# Khoi-nguon.net
KiCad netlist of a schematic drawn in Altium Designer
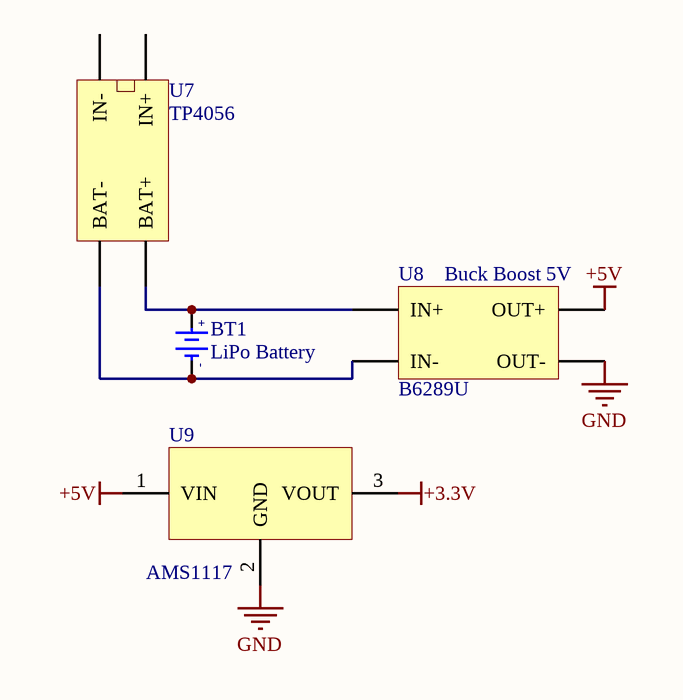
[diagram p0: Khoi-nguon.SchDoc]

(export (version "E")
  (design (tool "Eeschema 10.0.6"))
  (components
    (comp (ref "BT1")
      (value "LiPo Battery")
      (footprint "PIN3V")
      (description "Battery 3VDC")
      (libsource (lib "LIBRARY1") (part "PIN 3V"))
    )
    (comp (ref "U7")
      (value "TP4056")
      (description "Module sac pin")
      (libsource (lib "iuh-thuc-hanh") (part "TP4056"))
    )
    (comp (ref "U8")
      (value "B6289U")
      (description "Module Buck Boost 5V")
      (libsource (lib "iuh-thuc-hanh") (part "B6289U"))
    )
    (comp (ref "U9") (value "AMS1117") (libsource (lib "iuh-thuc-hanh") (part "AMS1117")))
  )
  (nets
    (net (code "1") (name "+3.3V") (class "Default")
      (node (ref "U9") (pin "3") (pinfunction "VOUT_3") (pintype "passive"))
    )
    (net (code "2") (name "+5V") (class "Default")
      (node (ref "U8") (pin "3") (pinfunction "OUT+_3") (pintype "passive"))
      (node (ref "U9") (pin "1") (pinfunction "VIN_1") (pintype "passive"))
    )
    (net (code "3") (name "GND") (class "Default")
      (node (ref "U8") (pin "4") (pinfunction "OUT-_4") (pintype "passive"))
      (node (ref "U9") (pin "2") (pinfunction "GND_2") (pintype "passive"))
    )
    (net (code "4") (name "Net-(BT1-+3V)") (class "Default")
      (node (ref "BT1") (pin "1") (pinfunction "+3V_1") (pintype "passive"))
      (node (ref "U7") (pin "2") (pinfunction "BAT+_2") (pintype "passive"))
      (node (ref "U8") (pin "1") (pinfunction "IN+_1") (pintype "passive"))
    )
    (net (code "5") (name "Net-(BT1-GND)") (class "Default")
      (node (ref "BT1") (pin "2") (pinfunction "GND_2") (pintype "passive"))
      (node (ref "U7") (pin "3") (pinfunction "BAT-_3") (pintype "passive"))
      (node (ref "U8") (pin "2") (pinfunction "IN-_2") (pintype "passive"))
    )
    (net (code "6") (name "unconnected-(U7-IN+-Pad3)") (class "Default")
      (node (ref "U7") (pin "3") (pinfunction "IN+_3") (pintype "passive"))
    )
    (net (code "7") (name "unconnected-(U7-IN--Pad2)") (class "Default")
      (node (ref "U7") (pin "2") (pinfunction "IN-_2") (pintype "passive"))
    )
  )
)
